# PSPS_AVNC_MITCH_2021-0_PRODUCTION.net
KiCad netlist of a schematic drawn in EAGLE
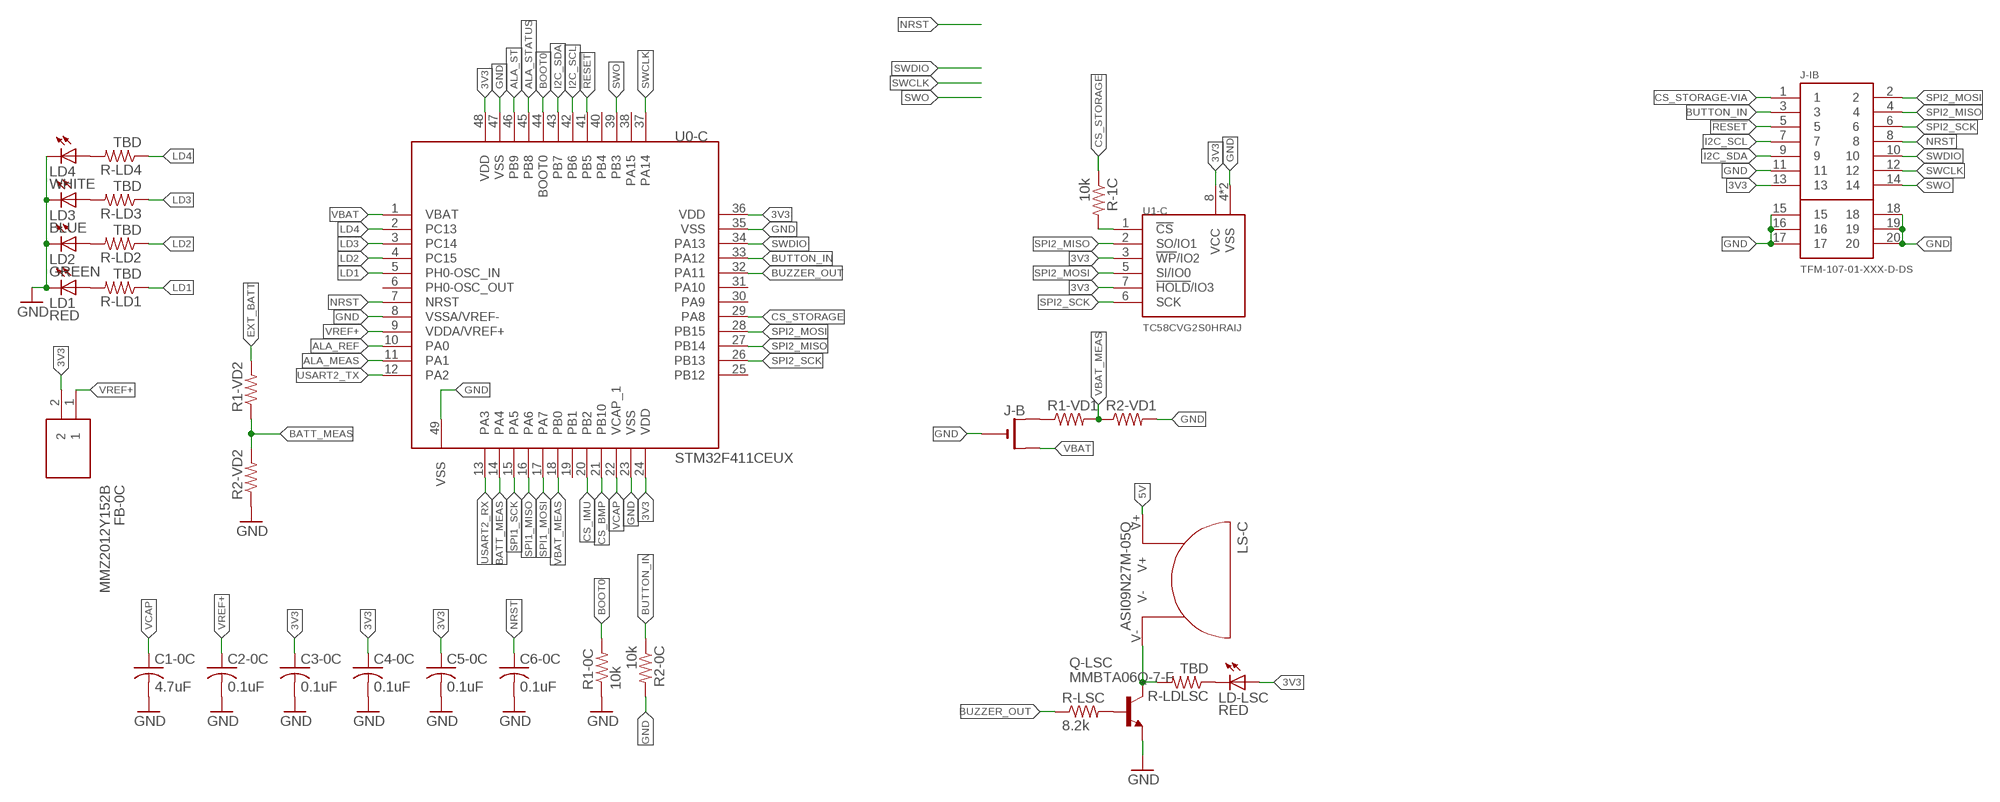
[diagram p0: schematic, sheet 1]
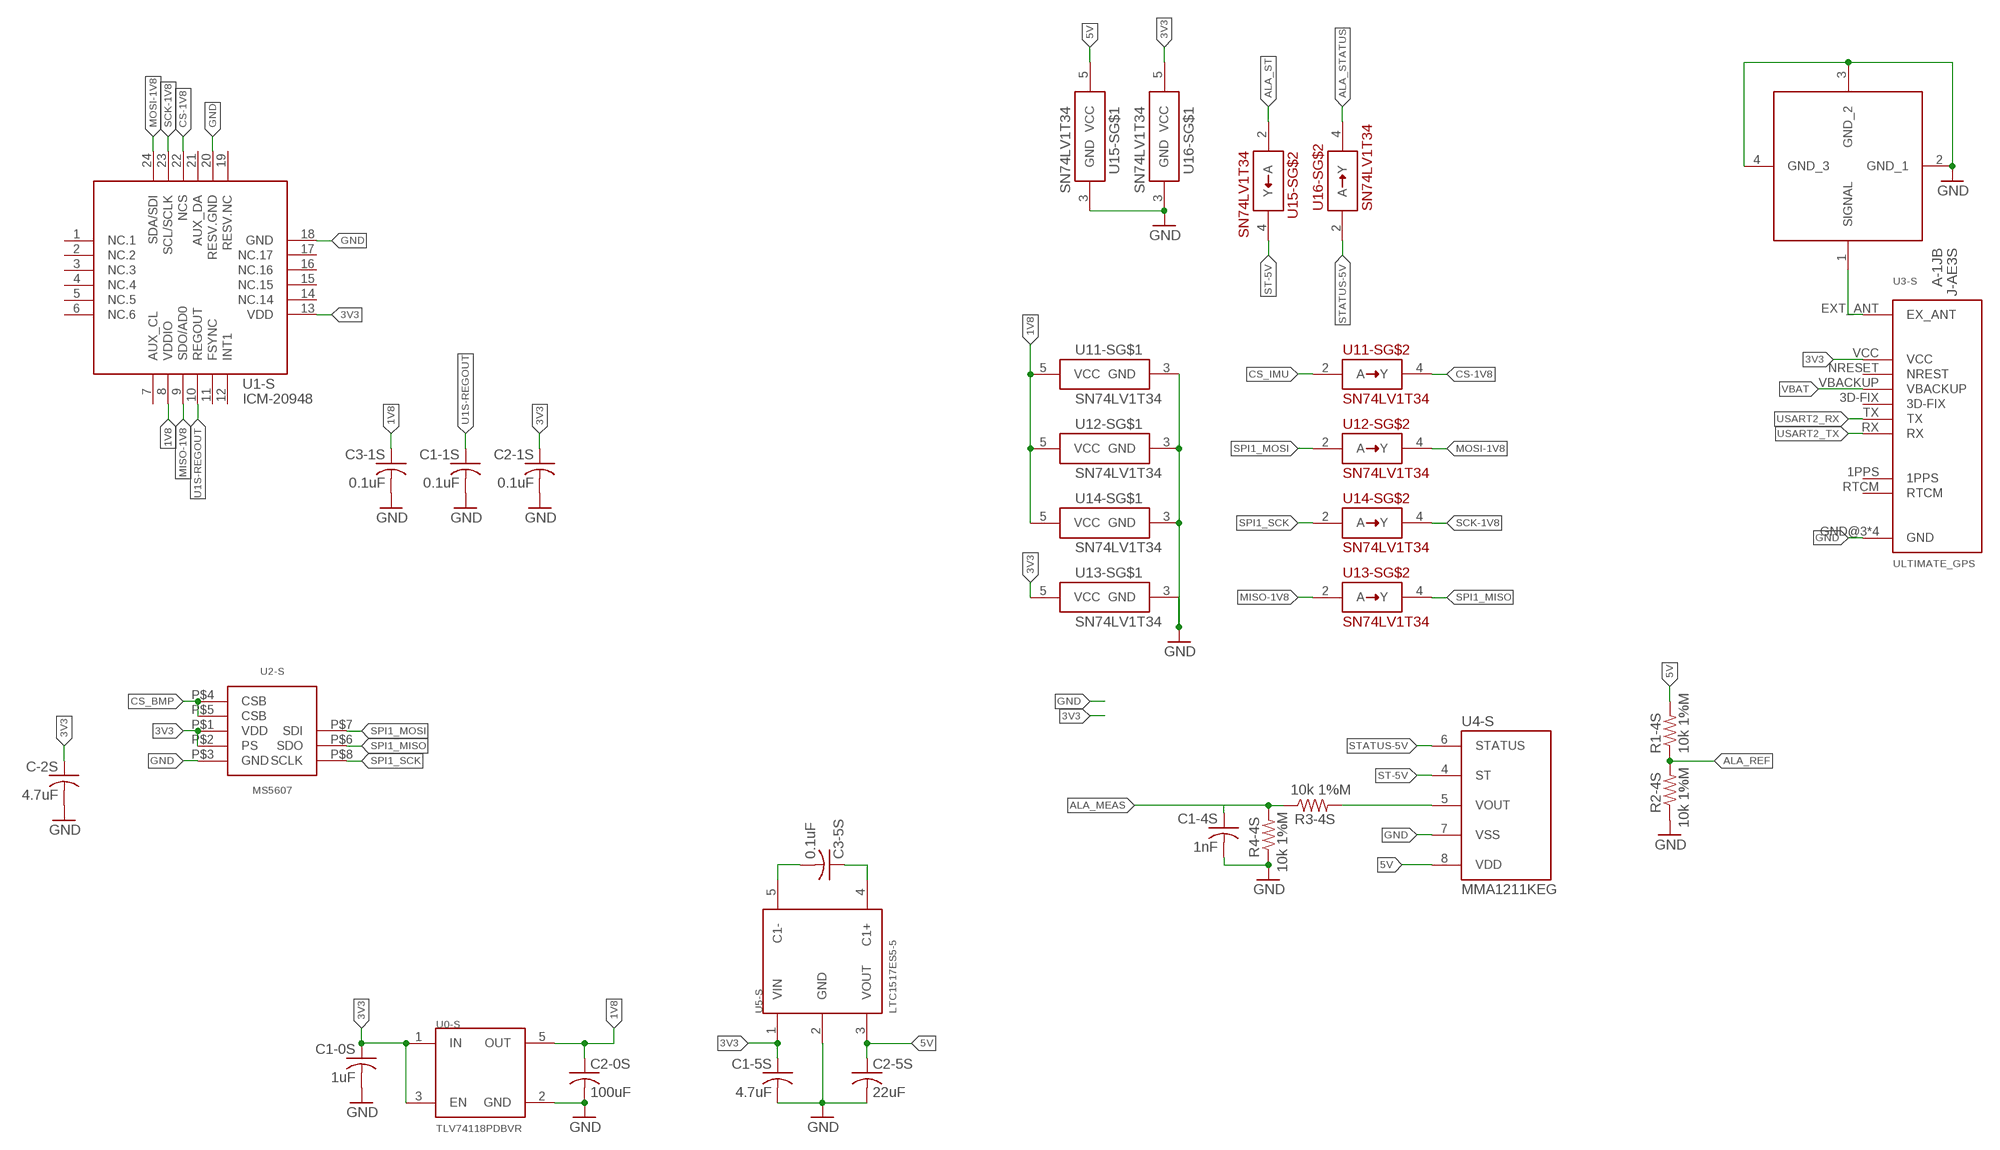
[diagram p1: schematic, sheet 2]

(export (version "E")
  (design (tool "Eeschema 10.0.6"))
  (components
    (comp (ref "C-2S")
      (value "4.7uF")
      (footprint "eagle-import:C0805")
      (libsource (lib "eagle-import") (part "C-USC0805"))
    )
    (comp (ref "C1-0S")
      (value "1uF")
      (footprint "eagle-import:C0805")
      (libsource (lib "eagle-import") (part "C-USC0805"))
    )
    (comp (ref "C1-1S")
      (value "0.1uF")
      (footprint "eagle-import:C0805")
      (libsource (lib "eagle-import") (part "C-USC0805"))
    )
    (comp (ref "C1-4S")
      (value "1nF")
      (footprint "eagle-import:C0805")
      (libsource (lib "eagle-import") (part "C-USC0805"))
    )
    (comp (ref "C1-5S")
      (value "4.7uF")
      (footprint "eagle-import:C0805")
      (libsource (lib "eagle-import") (part "C-USC0805"))
    )
    (comp (ref "C2-0S")
      (value "100uF")
      (footprint "eagle-import:C0805")
      (libsource (lib "eagle-import") (part "C-USC0805"))
    )
    (comp (ref "C2-1S")
      (value "0.1uF")
      (footprint "eagle-import:C0805")
      (libsource (lib "eagle-import") (part "C-USC0805"))
    )
    (comp (ref "C2-5S")
      (value "22uF")
      (footprint "eagle-import:C0805")
      (libsource (lib "eagle-import") (part "C-USC0805"))
    )
    (comp (ref "C3-1S")
      (value "0.1uF")
      (footprint "eagle-import:C0805")
      (libsource (lib "eagle-import") (part "C-USC0805"))
    )
    (comp (ref "C3-5S")
      (value "0.1uF")
      (footprint "eagle-import:C0805")
      (libsource (lib "eagle-import") (part "C-USC0805"))
    )
    (comp (ref "J-AE3S")
      (value "A-1JB")
      (footprint "eagle-import:A1JB")
      (fields (field (name "MOUSER_PART_NUMBER") "523-A-1JB"))
      (libsource (lib "eagle-import") (part "A-1JB"))
    )
    (comp (ref "R1-4S")
      (value "10k 1%M")
      (footprint "eagle-import:R0805")
      (libsource (lib "eagle-import") (part "R-US_R0805"))
    )
    (comp (ref "R2-4S")
      (value "10k 1%M")
      (footprint "eagle-import:R0805")
      (libsource (lib "eagle-import") (part "R-US_R0805"))
    )
    (comp (ref "R3-4S")
      (value "10k 1%M")
      (footprint "eagle-import:R0805")
      (libsource (lib "eagle-import") (part "R-US_R0805"))
    )
    (comp (ref "R4-4S")
      (value "10k 1%M")
      (footprint "eagle-import:R0805")
      (libsource (lib "eagle-import") (part "R-US_R0805"))
    )
    (comp (ref "U0-S")
      (value "TLV74118PDBVR")
      (footprint "eagle-import:SOT95P280X145-5N")
      (libsource (lib "eagle-import") (part "TLV74118PDBVR"))
    )
    (comp (ref "U1-S")
      (value "ICM-20948")
      (footprint "eagle-import:QFN40P300X300X105-25T159X175")
      (libsource (lib "eagle-import") (part "ICM-20948"))
    )
    (comp (ref "U2-S")
      (value "MS5607")
      (footprint "eagle-import:MS5607")
      (libsource (lib "eagle-import") (part "MS5607"))
    )
    (comp (ref "U3-S")
      (value "ULTIMATE_GPS")
      (footprint "eagle-import:FGPMMOPA6H")
      (libsource (lib "eagle-import") (part "ULTIMATE_GPS"))
    )
    (comp (ref "U4-S")
      (value "MMA1211KEG")
      (footprint "eagle-import:SOIC127P1041X355-16N")
      (libsource (lib "eagle-import") (part "MMA1211KEG"))
    )
    (comp (ref "U5-S")
      (value "LTC1517ES5-5")
      (footprint "eagle-import:SOT95P280X145-5N")
      (libsource (lib "eagle-import") (part "LTC1517ES5-5"))
    )
    (comp (ref "U11-S")
      (value "SN74LV1T34")
      (footprint "eagle-import:SOT65P210X110-5")
      (libsource (lib "eagle-import") (part "SN74LV1T34"))
    )
    (comp (ref "U12-S")
      (value "SN74LV1T34")
      (footprint "eagle-import:SOT65P210X110-5")
      (libsource (lib "eagle-import") (part "SN74LV1T34"))
    )
    (comp (ref "U13-S")
      (value "SN74LV1T34")
      (footprint "eagle-import:SOT65P210X110-5")
      (libsource (lib "eagle-import") (part "SN74LV1T34"))
    )
    (comp (ref "U14-S")
      (value "SN74LV1T34")
      (footprint "eagle-import:SOT65P210X110-5")
      (libsource (lib "eagle-import") (part "SN74LV1T34"))
    )
    (comp (ref "U15-S")
      (value "SN74LV1T34")
      (footprint "eagle-import:SOT65P210X110-5")
      (libsource (lib "eagle-import") (part "SN74LV1T34"))
    )
    (comp (ref "U16-S")
      (value "SN74LV1T34")
      (footprint "eagle-import:SOT65P210X110-5")
      (libsource (lib "eagle-import") (part "SN74LV1T34"))
    )
    (comp (ref "C1-0C")
      (value "4.7uF")
      (footprint "eagle-import:C0805")
      (libsource (lib "eagle-import") (part "C-USC0805"))
    )
    (comp (ref "C2-0C")
      (value "0.1uF")
      (footprint "eagle-import:C0805")
      (libsource (lib "eagle-import") (part "C-USC0805"))
    )
    (comp (ref "C3-0C")
      (value "0.1uF")
      (footprint "eagle-import:C0805")
      (libsource (lib "eagle-import") (part "C-USC0805"))
    )
    (comp (ref "C4-0C")
      (value "0.1uF")
      (footprint "eagle-import:C0805")
      (libsource (lib "eagle-import") (part "C-USC0805"))
    )
    (comp (ref "C5-0C")
      (value "0.1uF")
      (footprint "eagle-import:C0805")
      (libsource (lib "eagle-import") (part "C-USC0805"))
    )
    (comp (ref "C6-0C")
      (value "0.1uF")
      (footprint "eagle-import:C0805")
      (libsource (lib "eagle-import") (part "C-USC0805"))
    )
    (comp (ref "FB-0C")
      (value "MMZ2012Y152B")
      (footprint "eagle-import:BEADC2012X105N")
      (fields (field (name "MOUSER_PART_NUMBER") "810-MMZ2012Y152B"))
      (libsource (lib "eagle-import") (part "MMZ2012Y152B"))
    )
    (comp (ref "J-B")
      (value "CR1220SMT")
      (footprint "eagle-import:CR1220-SMD")
      (libsource (lib "eagle-import") (part "CR1220SMT"))
    )
    (comp (ref "J-IB")
      (value "TFM-107-01-XXX-D-DS")
      (footprint "eagle-import:TFM-107-01-XXX-D-DS")
      (libsource (lib "eagle-import") (part "TFM-107-01-XXX-D-DS"))
    )
    (comp (ref "LD-LSC")
      (value "RED")
      (footprint "eagle-import:CHIPLED_0805")
      (libsource (lib "eagle-import") (part "LEDCHIPLED_0805"))
    )
    (comp (ref "LD1")
      (value "RED")
      (footprint "eagle-import:CHIPLED_0805")
      (libsource (lib "eagle-import") (part "LEDCHIPLED_0805"))
    )
    (comp (ref "LD2")
      (value "GREEN")
      (footprint "eagle-import:CHIPLED_0805")
      (libsource (lib "eagle-import") (part "LEDCHIPLED_0805"))
    )
    (comp (ref "LD3")
      (value "BLUE")
      (footprint "eagle-import:CHIPLED_0805")
      (libsource (lib "eagle-import") (part "LEDCHIPLED_0805"))
    )
    (comp (ref "LD4")
      (value "WHITE")
      (footprint "eagle-import:CHIPLED_0805")
      (libsource (lib "eagle-import") (part "LEDCHIPLED_0805"))
    )
    (comp (ref "LS-C")
      (value "ASI09N27M-05Q")
      (footprint "eagle-import:ASI09N27M-05Q")
      (libsource (lib "eagle-import") (part "ASI09N27M-05Q"))
    )
    (comp (ref "Q-LSC")
      (value "MMBTA06Q-7-F")
      (footprint "eagle-import:SOT23")
      (libsource (lib "eagle-import") (part "NPN_TRANSISTOR"))
    )
    (comp (ref "R-1C")
      (value "10k")
      (footprint "eagle-import:R0805")
      (libsource (lib "eagle-import") (part "R-US_R0805"))
    )
    (comp (ref "R-LD1")
      (value "TBD")
      (footprint "eagle-import:R0805")
      (libsource (lib "eagle-import") (part "R-US_R0805"))
    )
    (comp (ref "R-LD2")
      (value "TBD")
      (footprint "eagle-import:R0805")
      (libsource (lib "eagle-import") (part "R-US_R0805"))
    )
    (comp (ref "R-LD3")
      (value "TBD")
      (footprint "eagle-import:R0805")
      (libsource (lib "eagle-import") (part "R-US_R0805"))
    )
    (comp (ref "R-LD4")
      (value "TBD")
      (footprint "eagle-import:R0805")
      (libsource (lib "eagle-import") (part "R-US_R0805"))
    )
    (comp (ref "R-LDLSC")
      (value "TBD")
      (footprint "eagle-import:R0805")
      (libsource (lib "eagle-import") (part "R-US_R0805"))
    )
    (comp (ref "R-LSC")
      (value "8.2k")
      (footprint "eagle-import:R0805")
      (libsource (lib "eagle-import") (part "R-US_R0805"))
    )
    (comp (ref "R1-0C")
      (value "10k")
      (footprint "eagle-import:R0805")
      (libsource (lib "eagle-import") (part "R-US_R0805"))
    )
    (comp (ref "R1-VD1")
      (value "R-US_R0805")
      (footprint "eagle-import:R0805")
      (libsource (lib "eagle-import") (part "R-US_R0805"))
    )
    (comp (ref "R1-VD2")
      (value "R-US_R0805")
      (footprint "eagle-import:R0805")
      (libsource (lib "eagle-import") (part "R-US_R0805"))
    )
    (comp (ref "R2-0C")
      (value "10k")
      (footprint "eagle-import:R0805")
      (libsource (lib "eagle-import") (part "R-US_R0805"))
    )
    (comp (ref "R2-VD1")
      (value "R-US_R0805")
      (footprint "eagle-import:R0805")
      (libsource (lib "eagle-import") (part "R-US_R0805"))
    )
    (comp (ref "R2-VD2")
      (value "R-US_R0805")
      (footprint "eagle-import:R0805")
      (libsource (lib "eagle-import") (part "R-US_R0805"))
    )
    (comp (ref "U0-C")
      (value "STM32F411CEUX")
      (footprint "eagle-import:QFN50P700X700X50-49T560N")
      (libsource (lib "eagle-import") (part "STM32F411CEUX"))
    )
    (comp (ref "U1-C")
      (value "TC58CVG2S0HRAIJ")
      (footprint "eagle-import:SON127P800X600X80-9T350X440N")
      (libsource (lib "eagle-import") (part "TC58CVG2S0HRAIJ"))
    )
  )
  (nets
    (net (code "1") (name "1V8") (class "Default")
      (node (ref "C2-0S") (pin "1") (pinfunction "1_1") (pintype "passive"))
      (node (ref "C3-1S") (pin "1") (pinfunction "1_1") (pintype "passive"))
      (node (ref "U0-S") (pin "5") (pinfunction "OUT_5") (pintype "bidirectional"))
      (node (ref "U1-S") (pin "8") (pinfunction "VDDIO_8") (pintype "bidirectional"))
      (node (ref "U11-S") (pin "5") (pinfunction "VCC_5") (pintype "bidirectional"))
      (node (ref "U12-S") (pin "5") (pinfunction "VCC_5") (pintype "bidirectional"))
      (node (ref "U14-S") (pin "5") (pinfunction "VCC_5") (pintype "bidirectional"))
    )
    (net (code "2") (name "3V3") (class "Default")
      (node (ref "C-2S") (pin "1") (pinfunction "1_1") (pintype "passive"))
      (node (ref "C1-0S") (pin "1") (pinfunction "1_1") (pintype "passive"))
      (node (ref "C1-5S") (pin "1") (pinfunction "1_1") (pintype "passive"))
      (node (ref "C2-1S") (pin "1") (pinfunction "1_1") (pintype "passive"))
      (node (ref "C3-0C") (pin "1") (pinfunction "1_1") (pintype "passive"))
      (node (ref "C4-0C") (pin "1") (pinfunction "1_1") (pintype "passive"))
      (node (ref "C5-0C") (pin "1") (pinfunction "1_1") (pintype "passive"))
      (node (ref "FB-0C") (pin "2") (pinfunction "2_2") (pintype "bidirectional"))
      (node (ref "J-IB") (pin "13") (pinfunction "13_13") (pintype "bidirectional"))
      (node (ref "LD-LSC") (pin "A") (pinfunction "A_A") (pintype "passive"))
      (node (ref "U0-C") (pin "24") (pinfunction "VDD_24") (pintype "bidirectional"))
      (node (ref "U0-C") (pin "36") (pinfunction "VDD_36") (pintype "bidirectional"))
      (node (ref "U0-C") (pin "48") (pinfunction "VDD_48") (pintype "bidirectional"))
      (node (ref "U0-S") (pin "1") (pinfunction "IN_1") (pintype "bidirectional"))
      (node (ref "U0-S") (pin "3") (pinfunction "EN_3") (pintype "bidirectional"))
      (node (ref "U1-C") (pin "3") (pinfunction "~{WP}/IO2_3") (pintype "bidirectional"))
      (node (ref "U1-C") (pin "7") (pinfunction "~{HOLD}/IO3_7") (pintype "bidirectional"))
      (node (ref "U1-C") (pin "8") (pinfunction "VCC_8") (pintype "bidirectional"))
      (node (ref "U1-S") (pin "13") (pinfunction "VDD_13") (pintype "bidirectional"))
      (node (ref "U13-S") (pin "5") (pinfunction "VCC_5") (pintype "bidirectional"))
      (node (ref "U16-S") (pin "5") (pinfunction "VCC_5") (pintype "bidirectional"))
      (node (ref "U2-S") (pin "P$1") (pinfunction "VDD_P$1") (pintype "bidirectional"))
      (node (ref "U2-S") (pin "P$2") (pinfunction "PS_P$2") (pintype "bidirectional"))
      (node (ref "U3-S") (pin "VCC") (pinfunction "VCC_VCC") (pintype "bidirectional"))
      (node (ref "U5-S") (pin "1") (pinfunction "VIN_1") (pintype "bidirectional"))
    )
    (net (code "3") (name "5V") (class "Default")
      (node (ref "C2-5S") (pin "1") (pinfunction "1_1") (pintype "passive"))
      (node (ref "LS-C") (pin "V+") (pinfunction "V+_V+") (pintype "bidirectional"))
      (node (ref "R1-4S") (pin "2") (pinfunction "2_2") (pintype "passive"))
      (node (ref "U15-S") (pin "5") (pinfunction "VCC_5") (pintype "bidirectional"))
      (node (ref "U4-S") (pin "8") (pinfunction "VDD_8") (pintype "bidirectional"))
      (node (ref "U5-S") (pin "3") (pinfunction "VOUT_3") (pintype "bidirectional"))
    )
    (net (code "4") (name "ALA_MEAS") (class "Default")
      (node (ref "C1-4S") (pin "1") (pinfunction "1_1") (pintype "passive"))
      (node (ref "R3-4S") (pin "1") (pinfunction "1_1") (pintype "passive"))
      (node (ref "R4-4S") (pin "2") (pinfunction "2_2") (pintype "passive"))
      (node (ref "U0-C") (pin "11") (pinfunction "PA1_11") (pintype "bidirectional"))
    )
    (net (code "5") (name "ALA_REF") (class "Default")
      (node (ref "R1-4S") (pin "1") (pinfunction "1_1") (pintype "passive"))
      (node (ref "R2-4S") (pin "2") (pinfunction "2_2") (pintype "passive"))
      (node (ref "U0-C") (pin "10") (pinfunction "PA0_10") (pintype "bidirectional"))
    )
    (net (code "6") (name "ALA_ST") (class "Default")
      (node (ref "U0-C") (pin "46") (pinfunction "PB9_46") (pintype "bidirectional"))
      (node (ref "U15-S") (pin "2") (pinfunction "A_2") (pintype "bidirectional"))
    )
    (net (code "7") (name "ALA_STATUS") (class "Default")
      (node (ref "U0-C") (pin "45") (pinfunction "PB8_45") (pintype "bidirectional"))
      (node (ref "U16-S") (pin "4") (pinfunction "Y_4") (pintype "bidirectional"))
    )
    (net (code "8") (name "BATT_MEAS") (class "Default")
      (node (ref "R1-VD2") (pin "1") (pinfunction "1_1") (pintype "passive"))
      (node (ref "R2-VD2") (pin "2") (pinfunction "2_2") (pintype "passive"))
      (node (ref "U0-C") (pin "14") (pinfunction "PA4_14") (pintype "bidirectional"))
    )
    (net (code "9") (name "BOOT0") (class "Default")
      (node (ref "R1-0C") (pin "2") (pinfunction "2_2") (pintype "passive"))
      (node (ref "U0-C") (pin "44") (pinfunction "BOOT0_44") (pintype "bidirectional"))
    )
    (net (code "10") (name "BUTTON_IN") (class "Default")
      (node (ref "J-IB") (pin "3") (pinfunction "3_3") (pintype "bidirectional"))
      (node (ref "R2-0C") (pin "1") (pinfunction "1_1") (pintype "passive"))
      (node (ref "U0-C") (pin "33") (pinfunction "PA12_33") (pintype "bidirectional"))
    )
    (net (code "11") (name "BUZZER_OUT") (class "Default")
      (node (ref "R-LSC") (pin "1") (pinfunction "1_1") (pintype "passive"))
      (node (ref "U0-C") (pin "32") (pinfunction "PA11_32") (pintype "bidirectional"))
    )
    (net (code "12") (name "CS-1V8") (class "Default")
      (node (ref "U1-S") (pin "22") (pinfunction "NCS_22") (pintype "bidirectional"))
      (node (ref "U11-S") (pin "4") (pinfunction "Y_4") (pintype "bidirectional"))
    )
    (net (code "13") (name "CS_BMP") (class "Default")
      (node (ref "U0-C") (pin "21") (pinfunction "PB10_21") (pintype "bidirectional"))
      (node (ref "U2-S") (pin "P$4") (pinfunction "CSB_P$4") (pintype "bidirectional"))
      (node (ref "U2-S") (pin "P$5") (pinfunction "CSB_P$5") (pintype "bidirectional"))
    )
    (net (code "14") (name "CS_IMU") (class "Default")
      (node (ref "U0-C") (pin "20") (pinfunction "PB2_20") (pintype "bidirectional"))
      (node (ref "U11-S") (pin "2") (pinfunction "A_2") (pintype "bidirectional"))
    )
    (net (code "15") (name "CS_STORAGE") (class "Default")
      (node (ref "R-1C") (pin "1") (pinfunction "1_1") (pintype "passive"))
      (node (ref "U0-C") (pin "29") (pinfunction "PA8_29") (pintype "bidirectional"))
    )
    (net (code "16") (name "CS_STORAGE-VIA") (class "Default")
      (node (ref "J-IB") (pin "1") (pinfunction "1_1") (pintype "bidirectional"))
      (node (ref "R-1C") (pin "2") (pinfunction "2_2") (pintype "passive"))
      (node (ref "U1-C") (pin "1") (pinfunction "~{CS}_1") (pintype "bidirectional"))
    )
    (net (code "17") (name "EXT_BATT") (class "Default")
      (node (ref "R1-VD2") (pin "2") (pinfunction "2_2") (pintype "passive"))
    )
    (net (code "18") (name "GND") (class "Default")
      (node (ref "C-2S") (pin "2") (pinfunction "2_2") (pintype "passive"))
      (node (ref "C1-0C") (pin "2") (pinfunction "2_2") (pintype "passive"))
      (node (ref "C1-0S") (pin "2") (pinfunction "2_2") (pintype "passive"))
      (node (ref "C1-1S") (pin "2") (pinfunction "2_2") (pintype "passive"))
      (node (ref "C1-4S") (pin "2") (pinfunction "2_2") (pintype "passive"))
      (node (ref "C1-5S") (pin "2") (pinfunction "2_2") (pintype "passive"))
      (node (ref "C2-0C") (pin "2") (pinfunction "2_2") (pintype "passive"))
      (node (ref "C2-0S") (pin "2") (pinfunction "2_2") (pintype "passive"))
      (node (ref "C2-1S") (pin "2") (pinfunction "2_2") (pintype "passive"))
      (node (ref "C2-5S") (pin "2") (pinfunction "2_2") (pintype "passive"))
      (node (ref "C3-0C") (pin "2") (pinfunction "2_2") (pintype "passive"))
      (node (ref "C3-1S") (pin "2") (pinfunction "2_2") (pintype "passive"))
      (node (ref "C4-0C") (pin "2") (pinfunction "2_2") (pintype "passive"))
      (node (ref "C5-0C") (pin "2") (pinfunction "2_2") (pintype "passive"))
      (node (ref "C6-0C") (pin "2") (pinfunction "2_2") (pintype "passive"))
      (node (ref "J-AE3S") (pin "2") (pinfunction "GND_1_2") (pintype "bidirectional"))
      (node (ref "J-AE3S") (pin "3") (pinfunction "GND_2_3") (pintype "bidirectional"))
      (node (ref "J-AE3S") (pin "4") (pinfunction "GND_3_4") (pintype "bidirectional"))
      (node (ref "J-B") (pin "-") (pinfunction "-_-") (pintype "passive"))
      (node (ref "J-IB") (pin "11") (pinfunction "11_11") (pintype "bidirectional"))
      (node (ref "J-IB") (pin "15") (pinfunction "15_15") (pintype "bidirectional"))
      (node (ref "J-IB") (pin "16") (pinfunction "16_16") (pintype "bidirectional"))
      (node (ref "J-IB") (pin "17") (pinfunction "17_17") (pintype "bidirectional"))
      (node (ref "J-IB") (pin "18") (pinfunction "18_18") (pintype "bidirectional"))
      (node (ref "J-IB") (pin "19") (pinfunction "19_19") (pintype "bidirectional"))
      (node (ref "J-IB") (pin "20") (pinfunction "20_20") (pintype "bidirectional"))
      (node (ref "LD1") (pin "C") (pinfunction "C_C") (pintype "passive"))
      (node (ref "LD2") (pin "C") (pinfunction "C_C") (pintype "passive"))
      (node (ref "LD3") (pin "C") (pinfunction "C_C") (pintype "passive"))
      (node (ref "LD4") (pin "C") (pinfunction "C_C") (pintype "passive"))
      (node (ref "Q-LSC") (pin "3") (pinfunction "E_3") (pintype "passive"))
      (node (ref "R1-0C") (pin "1") (pinfunction "1_1") (pintype "passive"))
      (node (ref "R2-0C") (pin "2") (pinfunction "2_2") (pintype "passive"))
      (node (ref "R2-4S") (pin "1") (pinfunction "1_1") (pintype "passive"))
      (node (ref "R2-VD1") (pin "2") (pinfunction "2_2") (pintype "passive"))
      (node (ref "R2-VD2") (pin "1") (pinfunction "1_1") (pintype "passive"))
      (node (ref "R4-4S") (pin "1") (pinfunction "1_1") (pintype "passive"))
      (node (ref "U0-C") (pin "23") (pinfunction "VSS_23") (pintype "bidirectional"))
      (node (ref "U0-C") (pin "35") (pinfunction "VSS_35") (pintype "bidirectional"))
      (node (ref "U0-C") (pin "47") (pinfunction "VSS_47") (pintype "bidirectional"))
      (node (ref "U0-C") (pin "49") (pinfunction "VSS_49") (pintype "bidirectional"))
      (node (ref "U0-C") (pin "8") (pinfunction "VSSA/VREF-_8") (pintype "bidirectional"))
      (node (ref "U0-S") (pin "2") (pinfunction "GND_2") (pintype "bidirectional"))
      (node (ref "U1-C") (pin "4") (pinfunction "VSS_4") (pintype "bidirectional"))
      (node (ref "U1-C") (pin "9") (pinfunction "VSS_9") (pintype "bidirectional"))
      (node (ref "U1-S") (pin "18") (pinfunction "GND_18") (pintype "bidirectional"))
      (node (ref "U1-S") (pin "20") (pinfunction "RESV.GND_20") (pintype "bidirectional"))
      (node (ref "U11-S") (pin "3") (pinfunction "GND_3") (pintype "bidirectional"))
      (node (ref "U12-S") (pin "3") (pinfunction "GND_3") (pintype "bidirectional"))
      (node (ref "U13-S") (pin "3") (pinfunction "GND_3") (pintype "bidirectional"))
      (node (ref "U14-S") (pin "3") (pinfunction "GND_3") (pintype "bidirectional"))
      (node (ref "U15-S") (pin "3") (pinfunction "GND_3") (pintype "bidirectional"))
      (node (ref "U16-S") (pin "3") (pinfunction "GND_3") (pintype "bidirectional"))
      (node (ref "U2-S") (pin "P$3") (pinfunction "GND_P$3") (pintype "bidirectional"))
      (node (ref "U3-S") (pin "GND@12") (pinfunction "GND_GND@12") (pintype "bidirectional"))
      (node (ref "U3-S") (pin "GND@19") (pinfunction "GND_GND@19") (pintype "bidirectional"))
      (node (ref "U3-S") (pin "GND@3") (pinfunction "GND_GND@3") (pintype "bidirectional"))
      (node (ref "U3-S") (pin "GND@8") (pinfunction "GND_GND@8") (pintype "bidirectional"))
      (node (ref "U4-S") (pin "7") (pinfunction "VSS_7") (pintype "bidirectional"))
      (node (ref "U5-S") (pin "2") (pinfunction "GND_2") (pintype "bidirectional"))
    )
    (net (code "19") (name "I2C_SCL") (class "Default")
      (node (ref "J-IB") (pin "7") (pinfunction "7_7") (pintype "bidirectional"))
      (node (ref "U0-C") (pin "42") (pinfunction "PB6_42") (pintype "bidirectional"))
    )
    (net (code "20") (name "I2C_SDA") (class "Default")
      (node (ref "J-IB") (pin "9") (pinfunction "9_9") (pintype "bidirectional"))
      (node (ref "U0-C") (pin "43") (pinfunction "PB7_43") (pintype "bidirectional"))
    )
    (net (code "21") (name "LD1") (class "Default")
      (node (ref "R-LD1") (pin "1") (pinfunction "1_1") (pintype "passive"))
      (node (ref "U0-C") (pin "5") (pinfunction "PH0-OSC_IN_5") (pintype "bidirectional"))
    )
    (net (code "22") (name "LD2") (class "Default")
      (node (ref "R-LD2") (pin "1") (pinfunction "1_1") (pintype "passive"))
      (node (ref "U0-C") (pin "4") (pinfunction "PC15_4") (pintype "bidirectional"))
    )
    (net (code "23") (name "LD3") (class "Default")
      (node (ref "R-LD3") (pin "1") (pinfunction "1_1") (pintype "passive"))
      (node (ref "U0-C") (pin "3") (pinfunction "PC14_3") (pintype "bidirectional"))
    )
    (net (code "24") (name "LD4") (class "Default")
      (node (ref "R-LD4") (pin "1") (pinfunction "1_1") (pintype "passive"))
      (node (ref "U0-C") (pin "2") (pinfunction "PC13_2") (pintype "bidirectional"))
    )
    (net (code "25") (name "MISO-1V8") (class "Default")
      (node (ref "U1-S") (pin "9") (pinfunction "SDO/AD0_9") (pintype "bidirectional"))
      (node (ref "U13-S") (pin "2") (pinfunction "A_2") (pintype "bidirectional"))
    )
    (net (code "26") (name "MOSI-1V8") (class "Default")
      (node (ref "U1-S") (pin "24") (pinfunction "SDA/SDI_24") (pintype "bidirectional"))
      (node (ref "U12-S") (pin "4") (pinfunction "Y_4") (pintype "bidirectional"))
    )
    (net (code "27") (name "NRST") (class "Default")
      (node (ref "C6-0C") (pin "1") (pinfunction "1_1") (pintype "passive"))
      (node (ref "J-IB") (pin "8") (pinfunction "8_8") (pintype "bidirectional"))
      (node (ref "U0-C") (pin "7") (pinfunction "NRST_7") (pintype "bidirectional"))
    )
    (net (code "28") (name "Net-(J-AE3S-SIGNAL)") (class "Default")
      (node (ref "J-AE3S") (pin "1") (pinfunction "SIGNAL_1") (pintype "bidirectional"))
      (node (ref "U3-S") (pin "EXT_ANT") (pinfunction "EX_ANT_EXT_ANT") (pintype "bidirectional"))
    )
    (net (code "29") (name "Net-(J-B-+)") (class "Default")
      (node (ref "J-B") (pin "+$1") (pinfunction "+_+$1") (pintype "passive"))
      (node (ref "R1-VD1") (pin "1") (pinfunction "1_1") (pintype "passive"))
    )
    (net (code "30") (name "Net-(LD-LSC-PadC)") (class "Default")
      (node (ref "LD-LSC") (pin "C") (pinfunction "C_C") (pintype "passive"))
      (node (ref "R-LDLSC") (pin "1") (pinfunction "1_1") (pintype "passive"))
    )
    (net (code "31") (name "Net-(LD1-PadA)") (class "Default")
      (node (ref "LD1") (pin "A") (pinfunction "A_A") (pintype "passive"))
      (node (ref "R-LD1") (pin "2") (pinfunction "2_2") (pintype "passive"))
    )
    (net (code "32") (name "Net-(LD2-PadA)") (class "Default")
      (node (ref "LD2") (pin "A") (pinfunction "A_A") (pintype "passive"))
      (node (ref "R-LD2") (pin "2") (pinfunction "2_2") (pintype "passive"))
    )
    (net (code "33") (name "Net-(LD3-PadA)") (class "Default")
      (node (ref "LD3") (pin "A") (pinfunction "A_A") (pintype "passive"))
      (node (ref "R-LD3") (pin "2") (pinfunction "2_2") (pintype "passive"))
    )
    (net (code "34") (name "Net-(LD4-PadA)") (class "Default")
      (node (ref "LD4") (pin "A") (pinfunction "A_A") (pintype "passive"))
      (node (ref "R-LD4") (pin "2") (pinfunction "2_2") (pintype "passive"))
    )
    (net (code "35") (name "Net-(Q-LSC-B)") (class "Default")
      (node (ref "Q-LSC") (pin "1") (pinfunction "B_1") (pintype "passive"))
      (node (ref "R-LSC") (pin "2") (pinfunction "2_2") (pintype "passive"))
    )
    (net (code "36") (name "Net-(Q-LSC-C)") (class "Default")
      (node (ref "LS-C") (pin "V-") (pinfunction "V-_V-") (pintype "bidirectional"))
      (node (ref "Q-LSC") (pin "2") (pinfunction "C_2") (pintype "passive"))
      (node (ref "R-LDLSC") (pin "2") (pinfunction "2_2") (pintype "passive"))
    )
    (net (code "37") (name "Net-(U4-S-VOUT)") (class "Default")
      (node (ref "R3-4S") (pin "2") (pinfunction "2_2") (pintype "passive"))
      (node (ref "U4-S") (pin "5") (pinfunction "VOUT_5") (pintype "bidirectional"))
    )
    (net (code "38") (name "Net-(U5-S-C1+)") (class "Default")
      (node (ref "C3-5S") (pin "1") (pinfunction "1_1") (pintype "passive"))
      (node (ref "U5-S") (pin "4") (pinfunction "C1+_4") (pintype "bidirectional"))
    )
    (net (code "39") (name "Net-(U5-S-C1-)") (class "Default")
      (node (ref "C3-5S") (pin "2") (pinfunction "2_2") (pintype "passive"))
      (node (ref "U5-S") (pin "5") (pinfunction "C1-_5") (pintype "bidirectional"))
    )
    (net (code "40") (name "SCK-1V8") (class "Default")
      (node (ref "U1-S") (pin "23") (pinfunction "SCL/SCLK_23") (pintype "bidirectional"))
      (node (ref "U14-S") (pin "4") (pinfunction "Y_4") (pintype "bidirectional"))
    )
    (net (code "41") (name "SPI1_MISO") (class "Default")
      (node (ref "U0-C") (pin "16") (pinfunction "PA6_16") (pintype "bidirectional"))
      (node (ref "U13-S") (pin "4") (pinfunction "Y_4") (pintype "bidirectional"))
      (node (ref "U2-S") (pin "P$6") (pinfunction "SDO_P$6") (pintype "bidirectional"))
    )
    (net (code "42") (name "SPI1_MOSI") (class "Default")
      (node (ref "U0-C") (pin "17") (pinfunction "PA7_17") (pintype "bidirectional"))
      (node (ref "U12-S") (pin "2") (pinfunction "A_2") (pintype "bidirectional"))
      (node (ref "U2-S") (pin "P$7") (pinfunction "SDI_P$7") (pintype "bidirectional"))
    )
    (net (code "43") (name "SPI1_SCK") (class "Default")
      (node (ref "U0-C") (pin "15") (pinfunction "PA5_15") (pintype "bidirectional"))
      (node (ref "U14-S") (pin "2") (pinfunction "A_2") (pintype "bidirectional"))
      (node (ref "U2-S") (pin "P$8") (pinfunction "SCLK_P$8") (pintype "bidirectional"))
    )
    (net (code "44") (name "SPI2_MISO") (class "Default")
      (node (ref "J-IB") (pin "4") (pinfunction "4_4") (pintype "bidirectional"))
      (node (ref "U0-C") (pin "27") (pinfunction "PB14_27") (pintype "bidirectional"))
      (node (ref "U1-C") (pin "2") (pinfunction "SO/IO1_2") (pintype "bidirectional"))
    )
    (net (code "45") (name "SPI2_MOSI") (class "Default")
      (node (ref "J-IB") (pin "2") (pinfunction "2_2") (pintype "bidirectional"))
      (node (ref "U0-C") (pin "28") (pinfunction "PB15_28") (pintype "bidirectional"))
      (node (ref "U1-C") (pin "5") (pinfunction "SI/IO0_5") (pintype "bidirectional"))
    )
    (net (code "46") (name "SPI2_SCK") (class "Default")
      (node (ref "J-IB") (pin "6") (pinfunction "6_6") (pintype "bidirectional"))
      (node (ref "U0-C") (pin "26") (pinfunction "PB13_26") (pintype "bidirectional"))
      (node (ref "U1-C") (pin "6") (pinfunction "SCK_6") (pintype "bidirectional"))
    )
    (net (code "47") (name "ST-5V") (class "Default")
      (node (ref "U15-S") (pin "4") (pinfunction "Y_4") (pintype "bidirectional"))
      (node (ref "U4-S") (pin "4") (pinfunction "ST_4") (pintype "bidirectional"))
    )
    (net (code "48") (name "STATUS-5V") (class "Default")
      (node (ref "U16-S") (pin "2") (pinfunction "A_2") (pintype "bidirectional"))
      (node (ref "U4-S") (pin "6") (pinfunction "STATUS_6") (pintype "bidirectional"))
    )
    (net (code "49") (name "SWCLK") (class "Default")
      (node (ref "J-IB") (pin "12") (pinfunction "12_12") (pintype "bidirectional"))
      (node (ref "U0-C") (pin "37") (pinfunction "PA14_37") (pintype "bidirectional"))
    )
    (net (code "50") (name "SWDIO") (class "Default")
      (node (ref "J-IB") (pin "10") (pinfunction "10_10") (pintype "bidirectional"))
      (node (ref "U0-C") (pin "34") (pinfunction "PA13_34") (pintype "bidirectional"))
    )
    (net (code "51") (name "SWO") (class "Default")
      (node (ref "J-IB") (pin "14") (pinfunction "14_14") (pintype "bidirectional"))
      (node (ref "U0-C") (pin "39") (pinfunction "PB3_39") (pintype "bidirectional"))
    )
    (net (code "52") (name "U1S-REGOUT") (class "Default")
      (node (ref "C1-1S") (pin "1") (pinfunction "1_1") (pintype "passive"))
      (node (ref "U1-S") (pin "10") (pinfunction "REGOUT_10") (pintype "bidirectional"))
    )
    (net (code "53") (name "USART2_RX") (class "Default")
      (node (ref "U0-C") (pin "13") (pinfunction "PA3_13") (pintype "bidirectional"))
      (node (ref "U3-S") (pin "TX") (pinfunction "TX_TX") (pintype "bidirectional"))
    )
    (net (code "54") (name "USART2_TX") (class "Default")
      (node (ref "U0-C") (pin "12") (pinfunction "PA2_12") (pintype "bidirectional"))
      (node (ref "U3-S") (pin "RX") (pinfunction "RX_RX") (pintype "bidirectional"))
    )
    (net (code "55") (name "VBAT") (class "Default")
      (node (ref "J-B") (pin "+$2") (pinfunction "+1_+$2") (pintype "passive"))
      (node (ref "U0-C") (pin "1") (pinfunction "VBAT_1") (pintype "bidirectional"))
      (node (ref "U3-S") (pin "VBACKUP") (pinfunction "VBACKUP_VBACKUP") (pintype "bidirectional"))
    )
    (net (code "56") (name "VBAT_MEAS") (class "Default")
      (node (ref "R1-VD1") (pin "2") (pinfunction "2_2") (pintype "passive"))
      (node (ref "R2-VD1") (pin "1") (pinfunction "1_1") (pintype "passive"))
      (node (ref "U0-C") (pin "18") (pinfunction "PB0_18") (pintype "bidirectional"))
    )
    (net (code "57") (name "VCAP") (class "Default")
      (node (ref "C1-0C") (pin "1") (pinfunction "1_1") (pintype "passive"))
      (node (ref "U0-C") (pin "22") (pinfunction "VCAP_1_22") (pintype "bidirectional"))
    )
    (net (code "58") (name "VREF+") (class "Default")
      (node (ref "C2-0C") (pin "1") (pinfunction "1_1") (pintype "passive"))
      (node (ref "FB-0C") (pin "1") (pinfunction "1_1") (pintype "bidirectional"))
      (node (ref "U0-C") (pin "9") (pinfunction "VDDA/VREF+_9") (pintype "bidirectional"))
    )
    (net (code "59") (name "unconnected-(U0-C-PA9-Pad30)") (class "Default")
      (node (ref "U0-C") (pin "30") (pinfunction "PA9_30") (pintype "bidirectional"))
    )
    (net (code "60") (name "unconnected-(U0-C-PA10-Pad31)") (class "Default")
      (node (ref "U0-C") (pin "31") (pinfunction "PA10_31") (pintype "bidirectional"))
    )
    (net (code "61") (name "unconnected-(U0-C-PA15-Pad38)") (class "Default")
      (node (ref "U0-C") (pin "38") (pinfunction "PA15_38") (pintype "bidirectional"))
    )
    (net (code "62") (name "unconnected-(U0-C-PB1-Pad19)") (class "Default")
      (node (ref "U0-C") (pin "19") (pinfunction "PB1_19") (pintype "bidirectional"))
    )
    (net (code "63") (name "unconnected-(U0-C-PB4-Pad40)") (class "Default")
      (node (ref "U0-C") (pin "40") (pinfunction "PB4_40") (pintype "bidirectional"))
    )
    (net (code "64") (name "unconnected-(U0-C-PB12-Pad25)") (class "Default")
      (node (ref "U0-C") (pin "25") (pinfunction "PB12_25") (pintype "bidirectional"))
    )
    (net (code "65") (name "unconnected-(U0-C-PH0-OSC_OUT-Pad6)") (class "Default")
      (node (ref "U0-C") (pin "6") (pinfunction "PH0-OSC_OUT_6") (pintype "bidirectional"))
    )
    (net (code "66") (name "unconnected-(U1-S-AUX_CL-Pad7)") (class "Default")
      (node (ref "U1-S") (pin "7") (pinfunction "AUX_CL_7") (pintype "bidirectional"))
    )
    (net (code "67") (name "unconnected-(U1-S-AUX_DA-Pad21)") (class "Default")
      (node (ref "U1-S") (pin "21") (pinfunction "AUX_DA_21") (pintype "bidirectional"))
    )
    (net (code "68") (name "unconnected-(U1-S-FSYNC-Pad11)") (class "Default")
      (node (ref "U1-S") (pin "11") (pinfunction "FSYNC_11") (pintype "bidirectional"))
    )
    (net (code "69") (name "unconnected-(U1-S-INT1-Pad12)") (class "Default")
      (node (ref "U1-S") (pin "12") (pinfunction "INT1_12") (pintype "bidirectional"))
    )
    (net (code "70") (name "unconnected-(U1-S-NC.1-Pad1)") (class "Default")
      (node (ref "U1-S") (pin "1") (pinfunction "NC.1_1") (pintype "bidirectional"))
    )
    (net (code "71") (name "unconnected-(U1-S-NC.2-Pad2)") (class "Default")
      (node (ref "U1-S") (pin "2") (pinfunction "NC.2_2") (pintype "bidirectional"))
    )
    (net (code "72") (name "unconnected-(U1-S-NC.3-Pad3)") (class "Default")
      (node (ref "U1-S") (pin "3") (pinfunction "NC.3_3") (pintype "bidirectional"))
    )
    (net (code "73") (name "unconnected-(U1-S-NC.4-Pad4)") (class "Default")
      (node (ref "U1-S") (pin "4") (pinfunction "NC.4_4") (pintype "bidirectional"))
    )
    (net (code "74") (name "unconnected-(U1-S-NC.5-Pad5)") (class "Default")
      (node (ref "U1-S") (pin "5") (pinfunction "NC.5_5") (pintype "bidirectional"))
    )
    (net (code "75") (name "unconnected-(U1-S-NC.6-Pad6)") (class "Default")
      (node (ref "U1-S") (pin "6") (pinfunction "NC.6_6") (pintype "bidirectional"))
    )
    (net (code "76") (name "unconnected-(U1-S-NC.14-Pad14)") (class "Default")
      (node (ref "U1-S") (pin "14") (pinfunction "NC.14_14") (pintype "bidirectional"))
    )
    (net (code "77") (name "unconnected-(U1-S-NC.15-Pad15)") (class "Default")
      (node (ref "U1-S") (pin "15") (pinfunction "NC.15_15") (pintype "bidirectional"))
    )
    (net (code "78") (name "unconnected-(U1-S-NC.16-Pad16)") (class "Default")
      (node (ref "U1-S") (pin "16") (pinfunction "NC.16_16") (pintype "bidirectional"))
    )
    (net (code "79") (name "unconnected-(U1-S-NC.17-Pad17)") (class "Default")
      (node (ref "U1-S") (pin "17") (pinfunction "NC.17_17") (pintype "bidirectional"))
    )
    (net (code "80") (name "unconnected-(U1-S-RESV.NC-Pad19)") (class "Default")
      (node (ref "U1-S") (pin "19") (pinfunction "RESV.NC_19") (pintype "bidirectional"))
    )
    (net (code "81") (name "unconnected-(U3-S-NREST-PadNRESET)") (class "Default")
      (node (ref "U3-S") (pin "NRESET") (pinfunction "NREST_NRESET") (pintype "bidirectional"))
    )
    (net (code "82") (name "unconnected-(U3-S-Pad1PPS)") (class "Default")
      (node (ref "U3-S") (pin "1PPS") (pinfunction "1PPS_1PPS") (pintype "bidirectional"))
    )
    (net (code "83") (name "unconnected-(U3-S-Pad3D-FIX)") (class "Default")
      (node (ref "U3-S") (pin "3D-FIX") (pinfunction "3D-FIX_3D-FIX") (pintype "bidirectional"))
    )
    (net (code "84") (name "unconnected-(U3-S-PadRTCM)") (class "Default")
      (node (ref "U3-S") (pin "RTCM") (pinfunction "RTCM_RTCM") (pintype "bidirectional"))
    )
    (net (code "85") (name "~{RESET}") (class "Default")
      (node (ref "J-IB") (pin "5") (pinfunction "5_5") (pintype "bidirectional"))
      (node (ref "U0-C") (pin "41") (pinfunction "PB5_41") (pintype "bidirectional"))
    )
  )
)
